# pad_v1.net
KiCad netlist of a schematic drawn in EAGLE
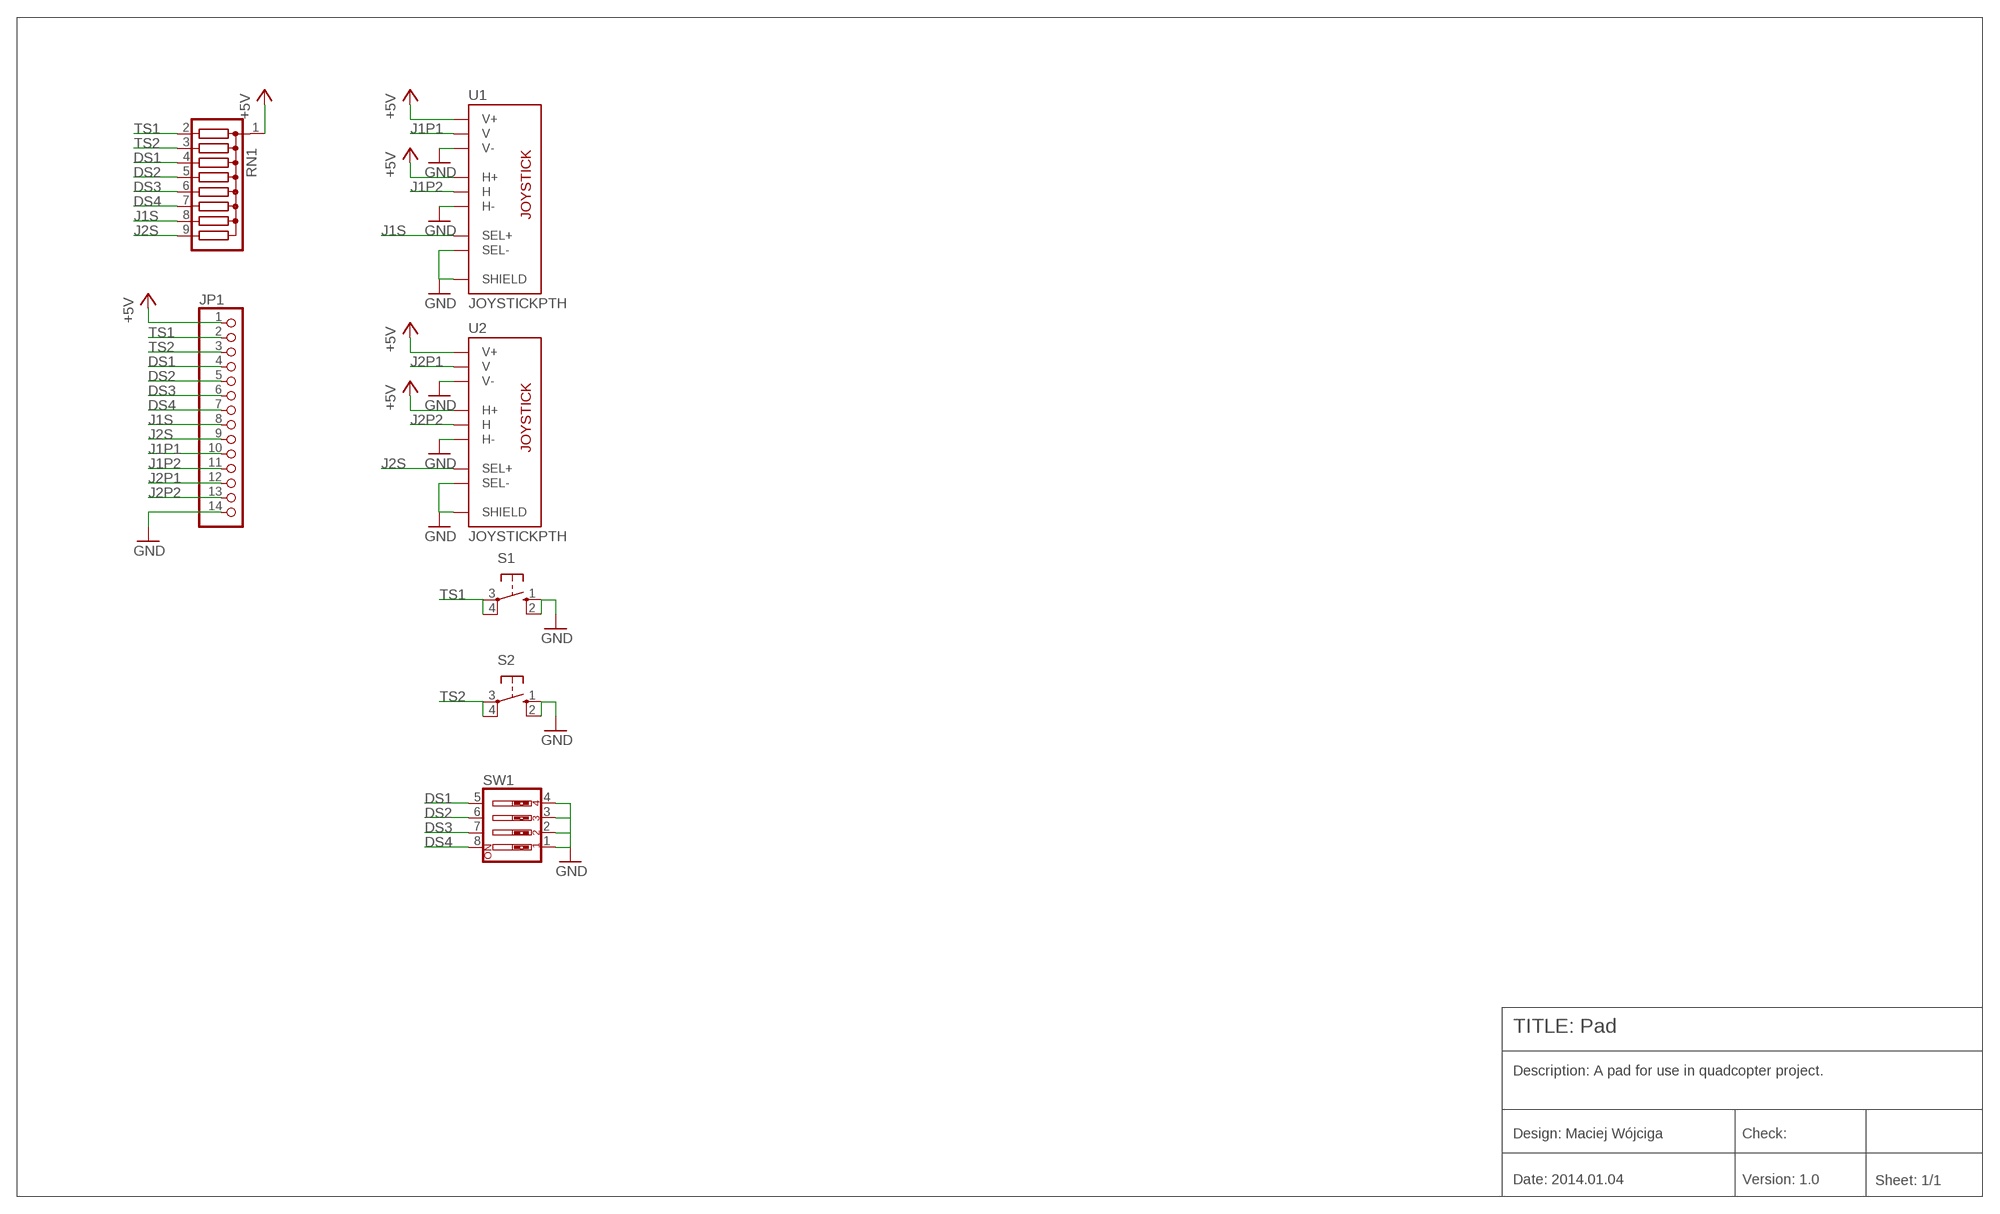
[diagram p0: schematic, sheet 1]

(export (version "E")
  (design (tool "Eeschema 10.0.6"))
  (components
    (comp (ref "JP1")
      (value "PINHD-1X14")
      (footprint "eagle-import:1X14")
      (libsource (lib "eagle-import") (part "PINHD-1X14"))
    )
    (comp (ref "RN1")
      (value "G08R")
      (footprint "eagle-import:SIL9")
      (libsource (lib "eagle-import") (part "G08R"))
    )
    (comp (ref "S1")
      (value "10-XX")
      (footprint "eagle-import:B3F-10XX")
      (fields (field (name "MPN") "B3F-1000"))
      (libsource (lib "eagle-import") (part "10-XX"))
    )
    (comp (ref "S2")
      (value "10-XX")
      (footprint "eagle-import:B3F-10XX")
      (fields (field (name "MPN") "B3F-1000"))
      (libsource (lib "eagle-import") (part "10-XX"))
    )
    (comp (ref "SW1")
      (value "SW_DIP-4")
      (footprint "eagle-import:EDG-04")
      (libsource (lib "eagle-import") (part "SW_DIP-4"))
    )
    (comp (ref "U1")
      (value "JOYSTICKPTH")
      (footprint "eagle-import:JOYSTICK")
      (libsource (lib "eagle-import") (part "JOYSTICKPTH"))
    )
    (comp (ref "U2")
      (value "JOYSTICKPTH")
      (footprint "eagle-import:JOYSTICK")
      (libsource (lib "eagle-import") (part "JOYSTICKPTH"))
    )
  )
  (nets
    (net (code "1") (name "+5V") (class "Default")
      (node (ref "JP1") (pin "1") (pinfunction "1_1") (pintype "passive"))
      (node (ref "RN1") (pin "1") (pinfunction "1_1") (pintype "passive"))
      (node (ref "U1") (pin "H1") (pinfunction "H+_H1") (pintype "bidirectional"))
      (node (ref "U1") (pin "V1") (pinfunction "V+_V1") (pintype "bidirectional"))
      (node (ref "U2") (pin "H1") (pinfunction "H+_H1") (pintype "bidirectional"))
      (node (ref "U2") (pin "V1") (pinfunction "V+_V1") (pintype "bidirectional"))
    )
    (net (code "2") (name "/DS1") (class "Default")
      (node (ref "JP1") (pin "4") (pinfunction "4_4") (pintype "passive"))
      (node (ref "RN1") (pin "4") (pinfunction "4_4") (pintype "passive"))
      (node (ref "SW1") (pin "5") (pinfunction "5_5") (pintype "passive"))
    )
    (net (code "3") (name "/DS2") (class "Default")
      (node (ref "JP1") (pin "5") (pinfunction "5_5") (pintype "passive"))
      (node (ref "RN1") (pin "5") (pinfunction "5_5") (pintype "passive"))
      (node (ref "SW1") (pin "6") (pinfunction "6_6") (pintype "passive"))
    )
    (net (code "4") (name "/DS3") (class "Default")
      (node (ref "JP1") (pin "6") (pinfunction "6_6") (pintype "passive"))
      (node (ref "RN1") (pin "6") (pinfunction "6_6") (pintype "passive"))
      (node (ref "SW1") (pin "7") (pinfunction "7_7") (pintype "passive"))
    )
    (net (code "5") (name "/DS4") (class "Default")
      (node (ref "JP1") (pin "7") (pinfunction "7_7") (pintype "passive"))
      (node (ref "RN1") (pin "7") (pinfunction "7_7") (pintype "passive"))
      (node (ref "SW1") (pin "8") (pinfunction "8_8") (pintype "passive"))
    )
    (net (code "6") (name "/J1P1") (class "Default")
      (node (ref "JP1") (pin "10") (pinfunction "10_10") (pintype "passive"))
      (node (ref "U1") (pin "V2") (pinfunction "V_V2") (pintype "bidirectional"))
    )
    (net (code "7") (name "/J1P2") (class "Default")
      (node (ref "JP1") (pin "11") (pinfunction "11_11") (pintype "passive"))
      (node (ref "U1") (pin "H2") (pinfunction "H_H2") (pintype "bidirectional"))
    )
    (net (code "8") (name "/J1S") (class "Default")
      (node (ref "JP1") (pin "8") (pinfunction "8_8") (pintype "passive"))
      (node (ref "RN1") (pin "8") (pinfunction "8_8") (pintype "passive"))
      (node (ref "U1") (pin "B1A") (pinfunction "SEL+_B1A") (pintype "bidirectional"))
      (node (ref "U1") (pin "B1B") (pinfunction "SEL+_B1B") (pintype "bidirectional"))
    )
    (net (code "9") (name "/J2P1") (class "Default")
      (node (ref "JP1") (pin "12") (pinfunction "12_12") (pintype "passive"))
      (node (ref "U2") (pin "V2") (pinfunction "V_V2") (pintype "bidirectional"))
    )
    (net (code "10") (name "/J2P2") (class "Default")
      (node (ref "JP1") (pin "13") (pinfunction "13_13") (pintype "passive"))
      (node (ref "U2") (pin "H2") (pinfunction "H_H2") (pintype "bidirectional"))
    )
    (net (code "11") (name "/J2S") (class "Default")
      (node (ref "JP1") (pin "9") (pinfunction "9_9") (pintype "passive"))
      (node (ref "RN1") (pin "9") (pinfunction "9_9") (pintype "passive"))
      (node (ref "U2") (pin "B1A") (pinfunction "SEL+_B1A") (pintype "bidirectional"))
      (node (ref "U2") (pin "B1B") (pinfunction "SEL+_B1B") (pintype "bidirectional"))
    )
    (net (code "12") (name "/TS1") (class "Default")
      (node (ref "JP1") (pin "2") (pinfunction "2_2") (pintype "passive"))
      (node (ref "RN1") (pin "2") (pinfunction "2_2") (pintype "passive"))
      (node (ref "S1") (pin "3") (pinfunction "P_3") (pintype "passive"))
      (node (ref "S1") (pin "4") (pinfunction "P1_4") (pintype "passive"))
    )
    (net (code "13") (name "/TS2") (class "Default")
      (node (ref "JP1") (pin "3") (pinfunction "3_3") (pintype "passive"))
      (node (ref "RN1") (pin "3") (pinfunction "3_3") (pintype "passive"))
      (node (ref "S2") (pin "3") (pinfunction "P_3") (pintype "passive"))
      (node (ref "S2") (pin "4") (pinfunction "P1_4") (pintype "passive"))
    )
    (net (code "14") (name "GND") (class "Default")
      (node (ref "JP1") (pin "14") (pinfunction "14_14") (pintype "passive"))
      (node (ref "S1") (pin "1") (pinfunction "S_1") (pintype "passive"))
      (node (ref "S1") (pin "2") (pinfunction "S1_2") (pintype "passive"))
      (node (ref "S2") (pin "1") (pinfunction "S_1") (pintype "passive"))
      (node (ref "S2") (pin "2") (pinfunction "S1_2") (pintype "passive"))
      (node (ref "SW1") (pin "1") (pinfunction "1_1") (pintype "passive"))
      (node (ref "SW1") (pin "2") (pinfunction "2_2") (pintype "passive"))
      (node (ref "SW1") (pin "3") (pinfunction "3_3") (pintype "passive"))
      (node (ref "SW1") (pin "4") (pinfunction "4_4") (pintype "passive"))
      (node (ref "U1") (pin "B2A") (pinfunction "SEL-_B2A") (pintype "bidirectional"))
      (node (ref "U1") (pin "B2B") (pinfunction "SEL-_B2B") (pintype "bidirectional"))
      (node (ref "U1") (pin "H3") (pinfunction "H-_H3") (pintype "bidirectional"))
      (node (ref "U1") (pin "MOUNT1") (pinfunction "SHIELD_MOUNT1") (pintype "bidirectional"))
      (node (ref "U1") (pin "MOUNT2") (pinfunction "SHIELD_MOUNT2") (pintype "bidirectional"))
      (node (ref "U1") (pin "MOUNT3") (pinfunction "SHIELD_MOUNT3") (pintype "bidirectional"))
      (node (ref "U1") (pin "MOUNT4") (pinfunction "SHIELD_MOUNT4") (pintype "bidirectional"))
      (node (ref "U1") (pin "V3") (pinfunction "V-_V3") (pintype "bidirectional"))
      (node (ref "U2") (pin "B2A") (pinfunction "SEL-_B2A") (pintype "bidirectional"))
      (node (ref "U2") (pin "B2B") (pinfunction "SEL-_B2B") (pintype "bidirectional"))
      (node (ref "U2") (pin "H3") (pinfunction "H-_H3") (pintype "bidirectional"))
      (node (ref "U2") (pin "MOUNT1") (pinfunction "SHIELD_MOUNT1") (pintype "bidirectional"))
      (node (ref "U2") (pin "MOUNT2") (pinfunction "SHIELD_MOUNT2") (pintype "bidirectional"))
      (node (ref "U2") (pin "MOUNT3") (pinfunction "SHIELD_MOUNT3") (pintype "bidirectional"))
      (node (ref "U2") (pin "MOUNT4") (pinfunction "SHIELD_MOUNT4") (pintype "bidirectional"))
      (node (ref "U2") (pin "V3") (pinfunction "V-_V3") (pintype "bidirectional"))
    )
  )
)
